# 02-MCU.net
KiCad netlist of a schematic drawn in Altium Designer
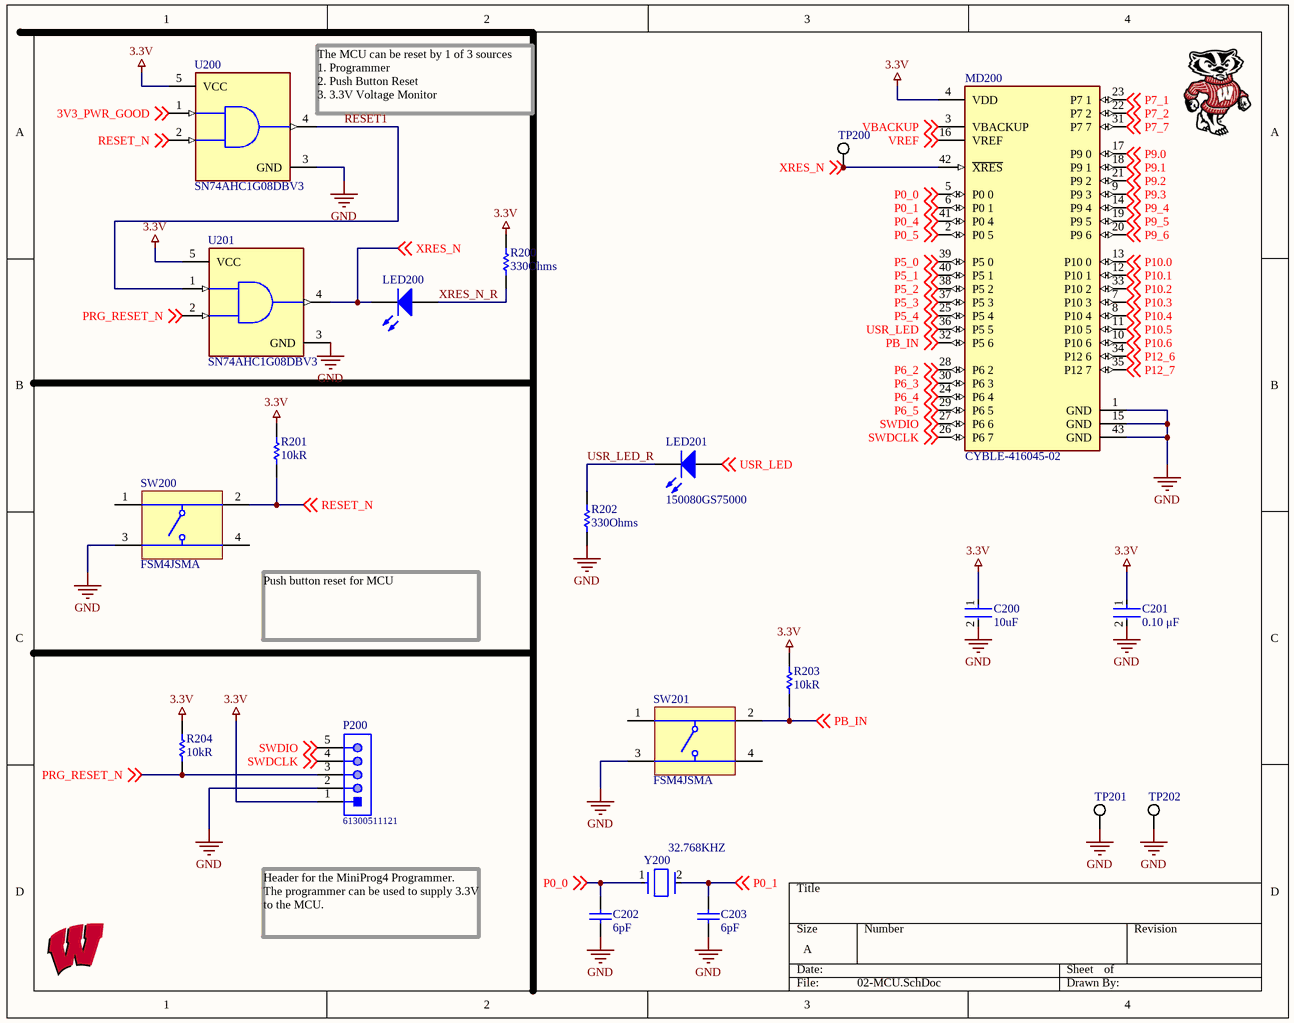
[diagram p0: 02-MCU.SchDoc]

(export (version "E")
  (design (tool "Eeschema 10.0.6"))
  (components
    (comp (ref "C200")
      (value "10uF")
      (footprint "FP-C0805C-DG-MFG")
      (description "CAP CER 10UF 10V X5R 0805")
      (fields (field (name "TOLERANCE") "10%") (field (name "MANUFACTURER PART NUMBER") "C0805C106K8PACTU"))
      (libsource (lib "Altium Content Vault") (part "11868f565c42a9108669ba33697ecf6"))
    )
    (comp (ref "C201")
      (value "0.10 μF")
      (footprint "FP-C0805C-DN-MFG")
      (description "CAP CER 0.1UF 50V X7R 0805")
      (fields
        (field (name "MANUFACTURER PART NUMBER") "C0805C104K5RACTU")
        (field (name "MANUFACTURER") "KEMET")
      )
      (libsource (lib "Altium Content Vault") (part "b4654b650e69147ec39a6b967a45e02"))
    )
    (comp (ref "C202")
      (value "08055A6R0CAT2A")
      (footprint "CAPC2013X94X50LL20T25")
      (fields (field (name "MANUFACTURER") "AVX Interconnect / Elco") (field (name "CAPACITANCE") "6pF"))
      (libsource (lib "Altium Content Vault") (part "CAP"))
    )
    (comp (ref "C203")
      (value "08055A6R0CAT2A")
      (footprint "CAPC2013X94X50LL20T25")
      (fields (field (name "MANUFACTURER") "AVX Interconnect / Elco") (field (name "CAPACITANCE") "6pF"))
      (libsource (lib "Altium Content Vault") (part "CAP"))
    )
    (comp (ref "LED200")
      (value "150080RS75000")
      (footprint "0805_A")
      (description "SMD mono-color Chip LED, WL-SMCW, Red")
      (fields (field (name "MANUFACTURER") "Wuerth Elektronik"))
      (libsource (lib "Altium Content Vault") (part "WE-LED_K1A2-2"))
    )
    (comp (ref "LED201")
      (value "150080GS75000")
      (footprint "0805_A")
      (description "SMD mono-color Chip LED, WL-SMCW, Green")
      (fields (field (name "MANUFACTURER") "Wuerth Elektronik"))
      (libsource (lib "Altium Content Vault") (part "WE-LED_K1A2-2"))
    )
    (comp (ref "MD200")
      (value "CYBLE-416045-02")
      (footprint "FP-CYBLE-416045-02-MFG")
      (description "RF TXRX MOD BLUETOOTH TRACE ANT")
      (fields
        (field (name "OCTOPART") "https://octopart.com/cyble-416045-02-cypress+semiconductor-96386825")
        (field (name "MANUFACTURER") "Cypress Semiconductor")
      )
      (libsource (lib "Altium Content Vault") (part "10a29a4e77099fbb6f911efb04878b1"))
    )
    (comp (ref "P200")
      (value "61300511121")
      (footprint "61300511121")
      (description "THT Vertical Pin Header WR-PHD, Pitch 2.54 mm, Single Row, 5 pins")
      (fields (field (name "MANUFACTURER") "Wurth Elektronik") (field (name "PUBLISHER") "WurthElektronik"))
      (libsource (lib "Altium Content Vault") (part "WE-CN-1P-M-R5"))
    )
    (comp (ref "R200")
      (value "RC0805FR-07330RL")
      (footprint "RESC2013X60X35LL10T20")
      (description "Chip Resistor, 330 Ohm, +/- 1%, 125 mW, -55 to 155 degC, 0805 (2012 Metric), RoHS, Tape and Reel")
      (fields
        (field (name "MANUFACTURER") "Yageo")
        (field (name "TOLERANCE") "1%")
        (field (name "RESISTANCE") "330Ohms")
      )
      (libsource (lib "Altium Content Vault") (part "RES-2"))
    )
    (comp (ref "R201")
      (value "RC0805FR-0710KL")
      (footprint "RESC2013X60X35NL10T20")
      (description "Chip Resistor, 10 KOhm, +/- 1%, 0.125 W, -55 to 155 degC, 0805 (2012 Metric), RoHS, Tape and Reel")
      (fields
        (field (name "MANUFACTURER") "Yageo")
        (field (name "RESISTANCE") "10kR")
        (field (name "TOLERANCE") "1%")
      )
      (libsource (lib "Altium Content Vault") (part "RES-2"))
    )
    (comp (ref "R202")
      (value "RC0805FR-07330RL")
      (footprint "RESC2013X60X35LL10T20")
      (description "Chip Resistor, 330 Ohm, +/- 1%, 125 mW, -55 to 155 degC, 0805 (2012 Metric), RoHS, Tape and Reel")
      (fields
        (field (name "MANUFACTURER") "Yageo")
        (field (name "TOLERANCE") "1%")
        (field (name "RESISTANCE") "330Ohms")
      )
      (libsource (lib "Altium Content Vault") (part "RES-2"))
    )
    (comp (ref "R203")
      (value "RC0805FR-0710KL")
      (footprint "RESC2013X60X35NL10T20")
      (description "Chip Resistor, 10 KOhm, +/- 1%, 0.125 W, -55 to 155 degC, 0805 (2012 Metric), RoHS, Tape and Reel")
      (fields
        (field (name "MANUFACTURER") "Yageo")
        (field (name "RESISTANCE") "10kR")
        (field (name "TOLERANCE") "1%")
      )
      (libsource (lib "Altium Content Vault") (part "RES-2"))
    )
    (comp (ref "R204")
      (value "RC0805FR-0710KL")
      (footprint "RESC2013X60X35NL10T20")
      (description "Chip Resistor, 10 KOhm, +/- 1%, 0.125 W, -55 to 155 degC, 0805 (2012 Metric), RoHS, Tape and Reel")
      (fields
        (field (name "MANUFACTURER") "Yageo")
        (field (name "RESISTANCE") "10kR")
        (field (name "TOLERANCE") "1%")
      )
      (libsource (lib "Altium Content Vault") (part "RES-2"))
    )
    (comp (ref "SW200")
      (value "FSM4JSMA")
      (footprint "TECO-FSM4JSMA_V")
      (description "Swicth, SPST, 24 V, -35 to 85 degC, 4-Pin SMD, RoHS, Tape and Reel")
      (fields (field (name "MANUFACTURER") "TE Connectivity"))
      (libsource (lib "Altium Content Vault") (part "SW-SPST-4_A"))
    )
    (comp (ref "SW201")
      (value "FSM4JSMA")
      (footprint "TECO-FSM4JSMA_V")
      (description "Swicth, SPST, 24 V, -35 to 85 degC, 4-Pin SMD, RoHS, Tape and Reel")
      (fields (field (name "MANUFACTURER") "TE Connectivity"))
      (libsource (lib "Altium Content Vault") (part "SW-SPST-4_A"))
    )
    (comp (ref "TP200")
      (value "5019")
      (footprint "KSTN-5019_V")
      (description "Test Point, 1 Position SMD, RoHS, Tape and Reel")
      (libsource (lib "Altium Content Vault") (part "TESTPOINT_WHITE"))
    )
    (comp (ref "TP201")
      (value "5019")
      (footprint "KSTN-5019_V")
      (description "Test Point, 1 Position SMD, RoHS, Tape and Reel")
      (libsource (lib "Altium Content Vault") (part "TESTPOINT_WHITE"))
    )
    (comp (ref "TP202")
      (value "5019")
      (footprint "KSTN-5019_V")
      (description "Test Point, 1 Position SMD, RoHS, Tape and Reel")
      (libsource (lib "Altium Content Vault") (part "TESTPOINT_WHITE"))
    )
    (comp (ref "U200")
      (value "SN74AHC1G08DBV3")
      (footprint "FP-DBV0005A-IPC_C")
      (description "IC GATE AND 1CH 2-INP SOT23-5")
      (libsource (lib "Altium Content Vault") (part "675e79b427d6219a5295bf943425e1c"))
    )
    (comp (ref "U201")
      (value "SN74AHC1G08DBV3")
      (footprint "FP-DBV0005A-IPC_C")
      (description "IC GATE AND 1CH 2-INP SOT23-5")
      (libsource (lib "Altium Content Vault") (part "675e79b427d6219a5295bf943425e1c"))
    )
    (comp (ref "Y200")
      (value "32.768KHZ")
      (footprint "FP-ABS07-120-MFG")
      (description "CRYSTAL 32.7680KHZ 6PF SMD")
      (fields (field (name "TOLERANCE") "20ppm"))
      (libsource (lib "Altium Content Vault") (part "c23a69dc6c9e2f18f2079038eb95dd1"))
    )
  )
  (nets
    (net (code "1") (name "/RESET1") (class "Default")
      (node (ref "U200") (pin "4") (pinfunction "Y_4") (pintype "output"))
      (node (ref "U201") (pin "1") (pinfunction "A_1") (pintype "input"))
    )
    (net (code "2") (name "/USR_LED_R") (class "Default")
      (node (ref "LED201") (pin "1") (pinfunction "K_1") (pintype "passive"))
      (node (ref "R202") (pin "2") (pinfunction "2_2") (pintype "passive"))
    )
    (net (code "3") (name "/XRES_N_R") (class "Default")
      (node (ref "LED200") (pin "2") (pinfunction "A_2") (pintype "passive"))
      (node (ref "R200") (pin "1") (pinfunction "1_1") (pintype "passive"))
    )
    (net (code "4") (name "3.3V") (class "Default")
      (node (ref "C200") (pin "1") (pinfunction "1_1") (pintype "passive"))
      (node (ref "C201") (pin "1") (pinfunction "1_1") (pintype "passive"))
      (node (ref "MD200") (pin "4") (pinfunction "VDD_4") (pintype "power_in"))
      (node (ref "P200") (pin "1") (pinfunction "1_1") (pintype "passive"))
      (node (ref "R200") (pin "2") (pinfunction "2_2") (pintype "passive"))
      (node (ref "R201") (pin "2") (pinfunction "2_2") (pintype "passive"))
      (node (ref "R203") (pin "2") (pinfunction "2_2") (pintype "passive"))
      (node (ref "R204") (pin "2") (pinfunction "2_2") (pintype "passive"))
      (node (ref "U200") (pin "5") (pinfunction "VCC_5") (pintype "power_in"))
      (node (ref "U201") (pin "5") (pinfunction "VCC_5") (pintype "power_in"))
    )
    (net (code "5") (name "3V3_PWR_GOOD") (class "Default")
      (node (ref "U200") (pin "1") (pinfunction "A_1") (pintype "input"))
    )
    (net (code "6") (name "GND") (class "Default")
      (node (ref "C200") (pin "2") (pinfunction "2_2") (pintype "passive"))
      (node (ref "C201") (pin "2") (pinfunction "2_2") (pintype "passive"))
      (node (ref "C202") (pin "1") (pinfunction "1_1") (pintype "passive"))
      (node (ref "C203") (pin "1") (pinfunction "1_1") (pintype "passive"))
      (node (ref "MD200") (pin "1") (pinfunction "GND_1") (pintype "power_in"))
      (node (ref "MD200") (pin "15") (pinfunction "GND_15") (pintype "power_in"))
      (node (ref "MD200") (pin "43") (pinfunction "GND_43") (pintype "power_in"))
      (node (ref "P200") (pin "2") (pinfunction "2_2") (pintype "passive"))
      (node (ref "R202") (pin "1") (pinfunction "1_1") (pintype "passive"))
      (node (ref "SW200") (pin "3") (pinfunction "3_3") (pintype "passive"))
      (node (ref "SW201") (pin "3") (pinfunction "3_3") (pintype "passive"))
      (node (ref "TP201") (pin "1") (pinfunction "1_1") (pintype "passive"))
      (node (ref "TP202") (pin "1") (pinfunction "1_1") (pintype "passive"))
      (node (ref "U200") (pin "3") (pinfunction "GND_3") (pintype "power_in"))
      (node (ref "U201") (pin "3") (pinfunction "GND_3") (pintype "power_in"))
    )
    (net (code "7") (name "P0_0") (class "Default")
      (node (ref "C202") (pin "2") (pinfunction "2_2") (pintype "passive"))
      (node (ref "MD200") (pin "5") (pinfunction "P0_0_5") (pintype "bidirectional"))
      (node (ref "Y200") (pin "1") (pinfunction "1_1") (pintype "passive"))
    )
    (net (code "8") (name "P0_1") (class "Default")
      (node (ref "C203") (pin "2") (pinfunction "2_2") (pintype "passive"))
      (node (ref "MD200") (pin "6") (pinfunction "P0_1_6") (pintype "bidirectional"))
      (node (ref "Y200") (pin "2") (pinfunction "2_2") (pintype "passive"))
    )
    (net (code "9") (name "P0_4") (class "Default")
      (node (ref "MD200") (pin "41") (pinfunction "P0_4_41") (pintype "bidirectional"))
    )
    (net (code "10") (name "P0_5") (class "Default")
      (node (ref "MD200") (pin "2") (pinfunction "P0_5_2") (pintype "bidirectional"))
    )
    (net (code "11") (name "P5_0") (class "Default")
      (node (ref "MD200") (pin "39") (pinfunction "P5_0_39") (pintype "bidirectional"))
    )
    (net (code "12") (name "P5_1") (class "Default")
      (node (ref "MD200") (pin "40") (pinfunction "P5_1_40") (pintype "bidirectional"))
    )
    (net (code "13") (name "P5_2") (class "Default")
      (node (ref "MD200") (pin "38") (pinfunction "P5_2_38") (pintype "bidirectional"))
    )
    (net (code "14") (name "P5_3") (class "Default")
      (node (ref "MD200") (pin "37") (pinfunction "P5_3_37") (pintype "bidirectional"))
    )
    (net (code "15") (name "P5_4") (class "Default")
      (node (ref "MD200") (pin "25") (pinfunction "P5_4_25") (pintype "bidirectional"))
    )
    (net (code "16") (name "P6_2") (class "Default")
      (node (ref "MD200") (pin "28") (pinfunction "P6_2_28") (pintype "bidirectional"))
    )
    (net (code "17") (name "P6_3") (class "Default")
      (node (ref "MD200") (pin "30") (pinfunction "P6_3_30") (pintype "bidirectional"))
    )
    (net (code "18") (name "P6_4") (class "Default")
      (node (ref "MD200") (pin "24") (pinfunction "P6_4_24") (pintype "bidirectional"))
    )
    (net (code "19") (name "P6_5") (class "Default")
      (node (ref "MD200") (pin "29") (pinfunction "P6_5_29") (pintype "bidirectional"))
    )
    (net (code "20") (name "P7_1") (class "Default")
      (node (ref "MD200") (pin "23") (pinfunction "P7_1_23") (pintype "bidirectional"))
    )
    (net (code "21") (name "P7_2") (class "Default")
      (node (ref "MD200") (pin "22") (pinfunction "P7_2_22") (pintype "bidirectional"))
    )
    (net (code "22") (name "P7_7") (class "Default")
      (node (ref "MD200") (pin "31") (pinfunction "P7_7_31") (pintype "bidirectional"))
    )
    (net (code "23") (name "P9.0") (class "Default")
      (node (ref "MD200") (pin "17") (pinfunction "P9_0_17") (pintype "bidirectional"))
    )
    (net (code "24") (name "P9.1") (class "Default")
      (node (ref "MD200") (pin "18") (pinfunction "P9_1_18") (pintype "bidirectional"))
    )
    (net (code "25") (name "P9.2") (class "Default")
      (node (ref "MD200") (pin "21") (pinfunction "P9_2_21") (pintype "bidirectional"))
    )
    (net (code "26") (name "P9.3") (class "Default")
      (node (ref "MD200") (pin "9") (pinfunction "P9_3_9") (pintype "bidirectional"))
    )
    (net (code "27") (name "P9_4") (class "Default")
      (node (ref "MD200") (pin "14") (pinfunction "P9_4_14") (pintype "bidirectional"))
    )
    (net (code "28") (name "P9_5") (class "Default")
      (node (ref "MD200") (pin "19") (pinfunction "P9_5_19") (pintype "bidirectional"))
    )
    (net (code "29") (name "P9_6") (class "Default")
      (node (ref "MD200") (pin "20") (pinfunction "P9_6_20") (pintype "bidirectional"))
    )
    (net (code "30") (name "P10.0") (class "Default")
      (node (ref "MD200") (pin "13") (pinfunction "P10_0_13") (pintype "bidirectional"))
    )
    (net (code "31") (name "P10.1") (class "Default")
      (node (ref "MD200") (pin "12") (pinfunction "P10_1_12") (pintype "bidirectional"))
    )
    (net (code "32") (name "P10.2") (class "Default")
      (node (ref "MD200") (pin "33") (pinfunction "P10_2_33") (pintype "bidirectional"))
    )
    (net (code "33") (name "P10.3") (class "Default")
      (node (ref "MD200") (pin "7") (pinfunction "P10_3_7") (pintype "bidirectional"))
    )
    (net (code "34") (name "P10.4") (class "Default")
      (node (ref "MD200") (pin "8") (pinfunction "P10_4_8") (pintype "bidirectional"))
    )
    (net (code "35") (name "P10.5") (class "Default")
      (node (ref "MD200") (pin "11") (pinfunction "P10_5_11") (pintype "bidirectional"))
    )
    (net (code "36") (name "P10.6") (class "Default")
      (node (ref "MD200") (pin "10") (pinfunction "P10_6_10") (pintype "bidirectional"))
    )
    (net (code "37") (name "P12_6") (class "Default")
      (node (ref "MD200") (pin "34") (pinfunction "P12_6_34") (pintype "bidirectional"))
    )
    (net (code "38") (name "P12_7") (class "Default")
      (node (ref "MD200") (pin "35") (pinfunction "P12_7_35") (pintype "bidirectional"))
    )
    (net (code "39") (name "PB_IN") (class "Default")
      (node (ref "MD200") (pin "32") (pinfunction "P5_6_32") (pintype "bidirectional"))
      (node (ref "R203") (pin "1") (pinfunction "1_1") (pintype "passive"))
      (node (ref "SW201") (pin "2") (pinfunction "2_2") (pintype "passive"))
    )
    (net (code "40") (name "PRG_RESET_N") (class "Default")
      (node (ref "P200") (pin "3") (pinfunction "3_3") (pintype "passive"))
      (node (ref "R204") (pin "1") (pinfunction "1_1") (pintype "passive"))
      (node (ref "U201") (pin "2") (pinfunction "B_2") (pintype "input"))
    )
    (net (code "41") (name "RESET_N") (class "Default")
      (node (ref "R201") (pin "1") (pinfunction "1_1") (pintype "passive"))
      (node (ref "SW200") (pin "2") (pinfunction "2_2") (pintype "passive"))
      (node (ref "U200") (pin "2") (pinfunction "B_2") (pintype "input"))
    )
    (net (code "42") (name "SWDCLK") (class "Default")
      (node (ref "MD200") (pin "26") (pinfunction "P6_7_26") (pintype "bidirectional"))
      (node (ref "P200") (pin "4") (pinfunction "4_4") (pintype "passive"))
    )
    (net (code "43") (name "SWDIO") (class "Default")
      (node (ref "MD200") (pin "27") (pinfunction "P6_6_27") (pintype "bidirectional"))
      (node (ref "P200") (pin "5") (pinfunction "5_5") (pintype "passive"))
    )
    (net (code "44") (name "USR_LED") (class "Default")
      (node (ref "LED201") (pin "2") (pinfunction "A_2") (pintype "passive"))
      (node (ref "MD200") (pin "36") (pinfunction "P5_5_36") (pintype "bidirectional"))
    )
    (net (code "45") (name "VBACKUP") (class "Default")
      (node (ref "MD200") (pin "3") (pinfunction "VBACKUP_3") (pintype "power_in"))
    )
    (net (code "46") (name "VREF") (class "Default")
      (node (ref "MD200") (pin "16") (pinfunction "VREF_16") (pintype "power_in"))
    )
    (net (code "47") (name "XRES_N") (class "Default")
      (node (ref "LED200") (pin "1") (pinfunction "K_1") (pintype "passive"))
      (node (ref "MD200") (pin "42") (pinfunction "~{XRES}_42") (pintype "input"))
      (node (ref "TP200") (pin "1") (pinfunction "1_1") (pintype "passive"))
      (node (ref "U201") (pin "4") (pinfunction "Y_4") (pintype "output"))
    )
    (net (code "48") (name "unconnected-(SW200-Pad1)") (class "Default")
      (node (ref "SW200") (pin "1") (pinfunction "1_1") (pintype "passive"))
    )
    (net (code "49") (name "unconnected-(SW200-Pad4)") (class "Default")
      (node (ref "SW200") (pin "4") (pinfunction "4_4") (pintype "passive"))
    )
    (net (code "50") (name "unconnected-(SW201-Pad1)") (class "Default")
      (node (ref "SW201") (pin "1") (pinfunction "1_1") (pintype "passive"))
    )
    (net (code "51") (name "unconnected-(SW201-Pad4)") (class "Default")
      (node (ref "SW201") (pin "4") (pinfunction "4_4") (pintype "passive"))
    )
  )
)
